# Switch_mode_power_supply.net
KiCad netlist of a schematic drawn in Altium Designer
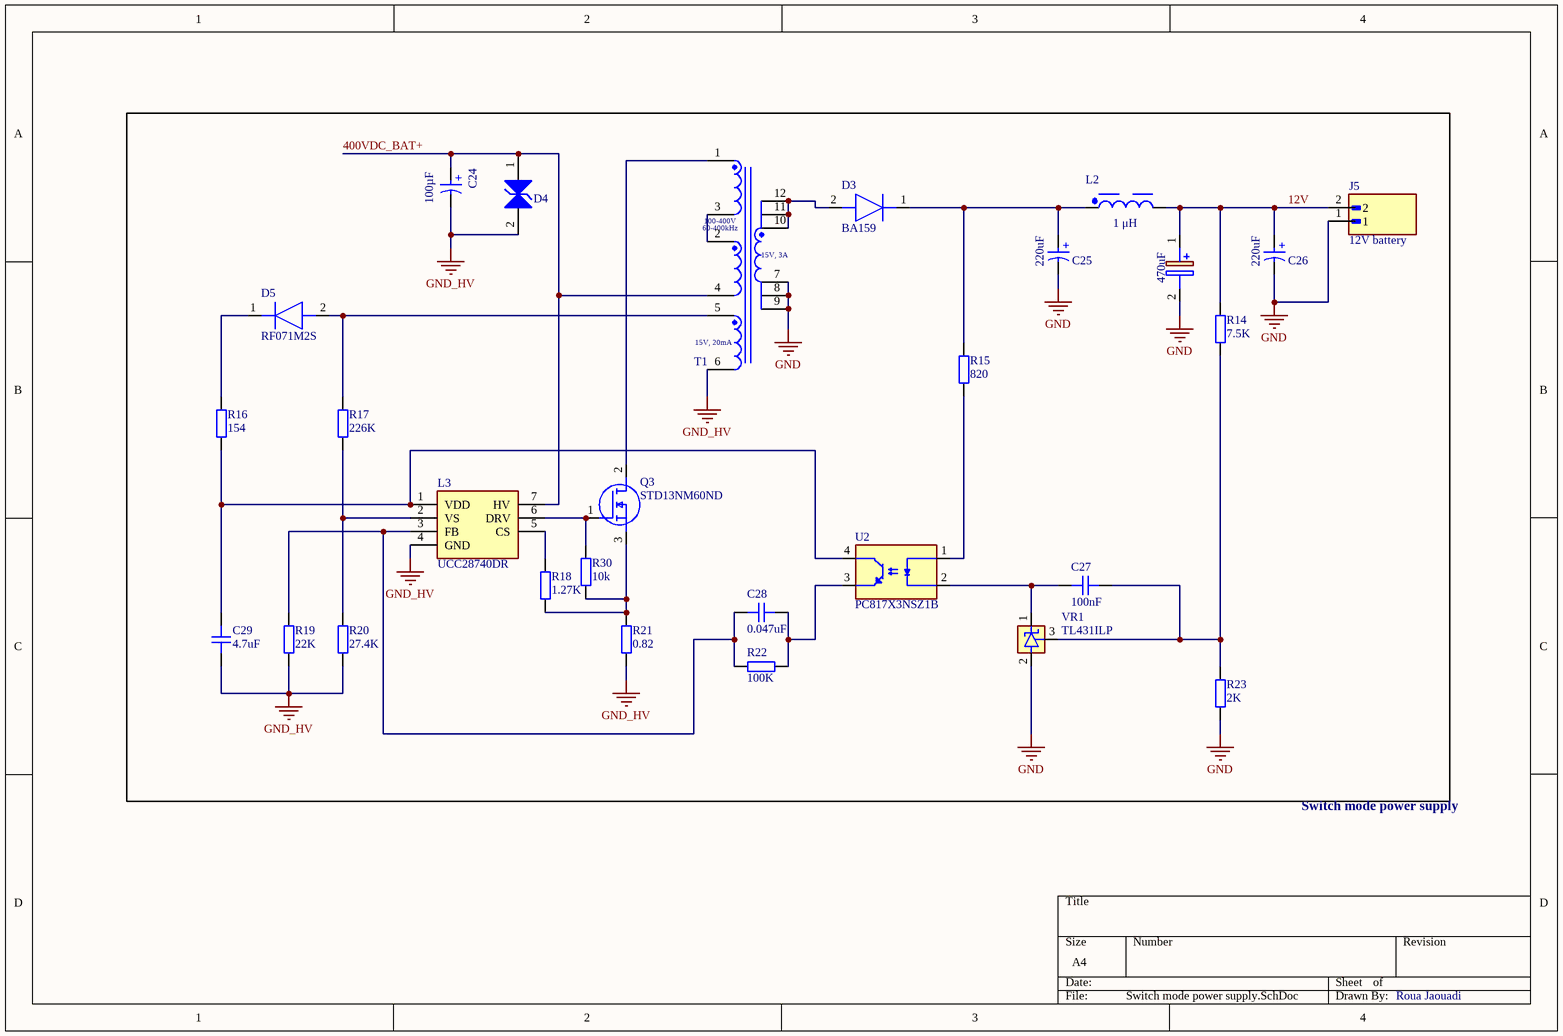
[diagram p0: Switch mode power supply.SchDoc]

(export (version "E")
  (design (tool "Eeschema 10.0.6"))
  (components
    (comp (ref "470uF")
      (value "UVR1C471MPD")
      (footprint "SamacSys:CAPPRD350W60D825H1300")
      (description "Capacitor Polarised")
      (libsource (lib "*") (part "UVR1C471MPD"))
    )
    (comp (ref "C24")
      (value "100µF")
      (footprint "WCAP-AT1H:WCAP-AT1H_D16H35.5")
      (description "WCAP-AT1H Aluminum Electrolytic Capacitor, Radial, D16 x H35.5mm, 100µF, 450V")
      (fields
        (field (name "MANUFACTURER PART NUMBER") "860241480001")
        (field (name "MANUFACTURER") "Wurth Elektronik")
      )
      (libsource (lib "WCAP-AT1H") (part "860241480001"))
    )
    (comp (ref "C25")
      (value "220uF")
      (footprint "WCAP-ATG8_D6.3H11")
      (description "WCAP-ATG8 Aluminum Electrolytic Capacitor, Radial, THT, D6.3 x H11mm, 220uF, 10V")
      (fields
        (field (name "MANUFACTURER PART NUMBER") "860010273009")
        (field (name "MANUFACTURER") "Wurth Elektronik")
      )
      (libsource (lib "Schlib1") (part "860010273009"))
    )
    (comp (ref "C26")
      (value "220uF")
      (footprint "WCAP-ATG8_D6.3H11")
      (description "WCAP-ATG8 Aluminum Electrolytic Capacitor, Radial, THT, D6.3 x H11mm, 220uF, 10V")
      (fields
        (field (name "MANUFACTURER PART NUMBER") "860010273009")
        (field (name "MANUFACTURER") "Wurth Elektronik")
      )
      (libsource (lib "Schlib1") (part "860010273009"))
    )
    (comp (ref "C27")
      (value "100nF")
      (footprint "CAP_1206")
      (description "Capacitor SMD 1206")
      (libsource (lib "Schematic-Lib-PhilsLab") (part "CAP_1206"))
    )
    (comp (ref "C28")
      (value "0.047uF")
      (footprint "CAP_1206")
      (description "Capacitor SMD 1206")
      (libsource (lib "Schematic-Lib-PhilsLab") (part "CAP_1206"))
    )
    (comp (ref "C29")
      (value "4.7uF")
      (footprint "CAP_1206")
      (description "Capacitor SMD 1206")
      (libsource (lib "Schematic-Lib-PhilsLab") (part "CAP_1206"))
    )
    (comp (ref "D3")
      (value "BA159")
      (footprint "SamacSys:DIOAD1405W86L465D235")
      (description "Diode")
      (fields (field (name "MOUSER PART NUMBER") "583-BA159"))
      (libsource (lib "SamacSys") (part "BA159"))
    )
    (comp (ref "D4")
      (value "600W, 5VDC")
      (footprint "WE-TVSP:WE-TVSP_DO-214AA_Bidirectional")
      (description "WE-TVSP SMT Power TVS Diode, DO-214AA, Bidirectional, 600W, 5VDC")
      (fields
        (field (name "MANUFACTURER PART NUMBER") "824521500")
        (field (name "MANUFACTURER") "Wurth Elektronik")
      )
      (libsource (lib "WE-TVSP") (part "824521500"))
    )
    (comp (ref "D5")
      (value "RF071M2S")
      (footprint "SamacSys:RF071M2S")
      (description "Diode")
      (libsource (lib "*") (part "RF071M2S"))
    )
    (comp (ref "J5")
      (value "12V battery")
      (footprint "JST_S2B-XH-A(LF)(SN):JST_S2B-XH-A(LF)(SN)")
      (description "Connector Header Through Hole, Right Angle 2 position 0.098 (2.50mm)")
      (fields (field (name "MF") "JST Sales") (field (name "MP") "S2B-XH-A(LF)(SN)"))
      (libsource (lib "S2B-XH-A(LF)(SN)") (part "S2B-XH-A(LF)(SN)"))
    )
    (comp (ref "L2")
      (value "1 μH")
      (footprint "WE-LHMI:WE-LHMI_1040")
      (description "WE-LHMI SMT Power Inductor, size 1040, 1 μH, 21.3 A, 3.3 mΩ")
      (fields
        (field (name "MANUFACTURER PART NUMBER") "74437368010")
        (field (name "MANUFACTURER") "Wurth Elektronik")
      )
      (libsource (lib "WE-LHMI") (part "74437368010"))
    )
    (comp (ref "L3")
      (value "UCC28740DR")
      (footprint "SamacSys:D(R-PDSO-G7)")
      (description "Inductor")
      (fields (field (name "MOUSER PART NUMBER") "595-UCC28740DR"))
      (libsource (lib "*") (part "UCC28740DR"))
    )
    (comp (ref "Q3")
      (value "STD13NM60ND")
      (footprint "SamacSys:STD13NM60ND")
      (description "MOSFET (N-Channel)")
      (fields (field (name "MOUSER PART NUMBER") "511-STD13NM60ND"))
      (libsource (lib "*") (part "STD13NM60ND"))
    )
    (comp (ref "R14")
      (value "7.5K")
      (footprint "RES_0603")
      (description "Resistor SMD 0603")
      (libsource (lib "Schlib1") (part "RES_0603"))
    )
    (comp (ref "R15")
      (value "820")
      (footprint "RES_0603")
      (description "Resistor SMD 0603")
      (libsource (lib "Schlib1") (part "RES_0603"))
    )
    (comp (ref "R16")
      (value "154")
      (footprint "RES_0603")
      (description "Resistor SMD 0603")
      (libsource (lib "Schlib1") (part "RES_0603"))
    )
    (comp (ref "R17")
      (value "226K")
      (footprint "RES_0603")
      (description "Resistor SMD 0603")
      (libsource (lib "Schlib1") (part "RES_0603"))
    )
    (comp (ref "R18")
      (value "1.27K")
      (footprint "RES_0603")
      (description "Resistor SMD 0603")
      (libsource (lib "Schlib1") (part "RES_0603"))
    )
    (comp (ref "R19")
      (value "22K")
      (footprint "RES_0603")
      (description "Resistor SMD 0603")
      (libsource (lib "Schlib1") (part "RES_0603"))
    )
    (comp (ref "R20")
      (value "27.4K")
      (footprint "RES_0603")
      (description "Resistor SMD 0603")
      (libsource (lib "Schlib1") (part "RES_0603"))
    )
    (comp (ref "R21")
      (value "0.82")
      (footprint "RES_0603")
      (description "Resistor SMD 0603")
      (libsource (lib "Schlib1") (part "RES_0603"))
    )
    (comp (ref "R22")
      (value "100K")
      (footprint "RES_0603")
      (description "Resistor SMD 0603")
      (libsource (lib "Schlib1") (part "RES_0603"))
    )
    (comp (ref "R23")
      (value "2K")
      (footprint "RES_0603")
      (description "Resistor SMD 0603")
      (libsource (lib "Schlib1") (part "RES_0603"))
    )
    (comp (ref "R30")
      (value "10k")
      (footprint "RES_0603")
      (description "Resistor SMD 0603")
      (libsource (lib "Schlib1") (part "RES_0603"))
    )
    (comp (ref "T1")
      (value "100-400Vin, Uo1 = 15V/3A")
      (footprint "WE-FB:WE-FB_EFD25")
      (description "WE-FB Flyback Transformer suitable for LT3748, SMT, EFD25, 100-400Vin, Uo1 = 15V/3A, 45W")
      (fields
        (field (name "MANUFACTURER PART NUMBER") "750311771")
        (field (name "MANUFACTURER") "Wurth Elektronik")
      )
      (libsource (lib "WE-FB") (part "750311771"))
    )
    (comp (ref "U2")
      (value "PC817X3NSZ1B")
      (footprint "DIP762W50P254L495H455Q4:DIP762W50P254L495H455Q4")
      (description "Optoisolator Transistor Output - 1 Channel 4-DIP")
      (fields (field (name "MF") "Sharp Microelectronics"))
      (libsource (lib "PC817X3NSZ1B") (part "PC817X3NSZ1B"))
    )
    (comp (ref "VR1")
      (value "TL431ILP")
      (footprint "VREG_TL431ILP:VREG_TL431ILP")
      (libsource (lib "TL431ILP") (part "TL431ILP"))
    )
  )
  (nets
    (net (code "1") (name "/12V") (class "Default")
      (node (ref "470uF") (pin "1") (pinfunction "+_1") (pintype "passive"))
      (node (ref "C26") (pin "1") (pinfunction "P_1") (pintype "passive"))
      (node (ref "J5") (pin "2") (pinfunction "2_2") (pintype "passive"))
      (node (ref "L2") (pin "2") (pinfunction "2_2") (pintype "passive"))
      (node (ref "R14") (pin "2") (pinfunction "2_2") (pintype "passive"))
    )
    (net (code "2") (name "/400VDC_BAT+") (class "Default")
      (node (ref "C24") (pin "1") (pinfunction "P_1") (pintype "passive"))
      (node (ref "D4") (pin "1") (pinfunction "1_1") (pintype "passive"))
      (node (ref "L3") (pin "7") (pinfunction "HV_7") (pintype "passive"))
      (node (ref "T1") (pin "4") (pinfunction "4_4") (pintype "passive"))
    )
    (net (code "3") (name "GND") (class "Default")
      (node (ref "470uF") (pin "2") (pinfunction "-_2") (pintype "passive"))
      (node (ref "C25") (pin "2") (pinfunction "N_2") (pintype "passive"))
      (node (ref "C26") (pin "2") (pinfunction "N_2") (pintype "passive"))
      (node (ref "J5") (pin "1") (pinfunction "1_1") (pintype "passive"))
      (node (ref "R23") (pin "1") (pinfunction "1_1") (pintype "passive"))
      (node (ref "T1") (pin "7") (pinfunction "7_7") (pintype "passive"))
      (node (ref "T1") (pin "8") (pinfunction "8_8") (pintype "passive"))
      (node (ref "T1") (pin "9") (pinfunction "9_9") (pintype "passive"))
      (node (ref "VR1") (pin "2") (pinfunction "ANODE_2") (pintype "passive"))
    )
    (net (code "4") (name "GND_HV") (class "Default")
      (node (ref "C24") (pin "2") (pinfunction "N_2") (pintype "passive"))
      (node (ref "C29") (pin "1") (pinfunction "1_1") (pintype "passive"))
      (node (ref "D4") (pin "2") (pinfunction "2_2") (pintype "passive"))
      (node (ref "L3") (pin "4") (pinfunction "GND_4") (pintype "passive"))
      (node (ref "R19") (pin "1") (pinfunction "1_1") (pintype "passive"))
      (node (ref "R20") (pin "1") (pinfunction "1_1") (pintype "passive"))
      (node (ref "R21") (pin "1") (pinfunction "1_1") (pintype "passive"))
      (node (ref "T1") (pin "6") (pinfunction "6_6") (pintype "passive"))
    )
    (net (code "5") (name "Net-(C25-P)") (class "Default")
      (node (ref "C25") (pin "1") (pinfunction "P_1") (pintype "passive"))
      (node (ref "D3") (pin "1") (pinfunction "K_1") (pintype "passive"))
      (node (ref "L2") (pin "1") (pinfunction "1_1") (pintype "passive"))
      (node (ref "R15") (pin "2") (pinfunction "2_2") (pintype "passive"))
    )
    (net (code "6") (name "Net-(D3-A)") (class "Default")
      (node (ref "D3") (pin "2") (pinfunction "A_2") (pintype "passive"))
      (node (ref "T1") (pin "10") (pinfunction "10_10") (pintype "passive"))
      (node (ref "T1") (pin "11") (pinfunction "11_11") (pintype "passive"))
      (node (ref "T1") (pin "12") (pinfunction "12_12") (pintype "passive"))
    )
    (net (code "7") (name "Net-(D5-A)") (class "Default")
      (node (ref "D5") (pin "2") (pinfunction "A_2") (pintype "passive"))
      (node (ref "R17") (pin "2") (pinfunction "2_2") (pintype "passive"))
      (node (ref "T1") (pin "5") (pinfunction "5_5") (pintype "passive"))
    )
    (net (code "8") (name "Net-(D5-K)") (class "Default")
      (node (ref "D5") (pin "1") (pinfunction "K_1") (pintype "passive"))
      (node (ref "R16") (pin "2") (pinfunction "2_2") (pintype "passive"))
    )
    (net (code "9") (name "Net-(L3-CS)") (class "Default")
      (node (ref "L3") (pin "5") (pinfunction "CS_5") (pintype "passive"))
      (node (ref "R18") (pin "1") (pinfunction "1_1") (pintype "passive"))
    )
    (net (code "10") (name "Net-(L3-DRV)") (class "Default")
      (node (ref "L3") (pin "6") (pinfunction "DRV_6") (pintype "passive"))
      (node (ref "Q3") (pin "1") (pinfunction "G_1") (pintype "passive"))
      (node (ref "R30") (pin "1") (pinfunction "1_1") (pintype "passive"))
    )
    (net (code "11") (name "Net-(L3-FB)") (class "Default")
      (node (ref "C28") (pin "2") (pinfunction "2_2") (pintype "passive"))
      (node (ref "L3") (pin "3") (pinfunction "FB_3") (pintype "passive"))
      (node (ref "R19") (pin "2") (pinfunction "2_2") (pintype "passive"))
      (node (ref "R22") (pin "2") (pinfunction "2_2") (pintype "passive"))
    )
    (net (code "12") (name "Net-(L3-VDD)") (class "Default")
      (node (ref "C29") (pin "2") (pinfunction "2_2") (pintype "passive"))
      (node (ref "L3") (pin "1") (pinfunction "VDD_1") (pintype "passive"))
      (node (ref "R16") (pin "1") (pinfunction "1_1") (pintype "passive"))
      (node (ref "U2") (pin "4") (pinfunction "COLLECTOR_4") (pintype "passive"))
    )
    (net (code "13") (name "Net-(L3-VS)") (class "Default")
      (node (ref "L3") (pin "2") (pinfunction "VS_2") (pintype "passive"))
      (node (ref "R17") (pin "1") (pinfunction "1_1") (pintype "passive"))
      (node (ref "R20") (pin "2") (pinfunction "2_2") (pintype "passive"))
    )
    (net (code "14") (name "Net-(Q3-D)") (class "Default")
      (node (ref "Q3") (pin "2") (pinfunction "D_2") (pintype "passive"))
      (node (ref "T1") (pin "1") (pinfunction "1_1") (pintype "passive"))
    )
    (net (code "15") (name "Net-(Q3-S)") (class "Default")
      (node (ref "Q3") (pin "3") (pinfunction "S_3") (pintype "passive"))
      (node (ref "R18") (pin "2") (pinfunction "2_2") (pintype "passive"))
      (node (ref "R21") (pin "2") (pinfunction "2_2") (pintype "passive"))
      (node (ref "R30") (pin "2") (pinfunction "2_2") (pintype "passive"))
    )
    (net (code "16") (name "Net-(T1-Pad2)") (class "Default")
      (node (ref "T1") (pin "2") (pinfunction "2_2") (pintype "passive"))
      (node (ref "T1") (pin "3") (pinfunction "3_3") (pintype "passive"))
    )
    (net (code "17") (name "Net-(U2-ANODE)") (class "Default")
      (node (ref "R15") (pin "1") (pinfunction "1_1") (pintype "passive"))
      (node (ref "U2") (pin "1") (pinfunction "ANODE_1") (pintype "passive"))
    )
    (net (code "18") (name "Net-(U2-CATHODE)") (class "Default")
      (node (ref "C27") (pin "2") (pinfunction "2_2") (pintype "passive"))
      (node (ref "U2") (pin "2") (pinfunction "CATHODE_2") (pintype "passive"))
      (node (ref "VR1") (pin "1") (pinfunction "CATHODE_1") (pintype "passive"))
    )
    (net (code "19") (name "Net-(U2-EMITTER)") (class "Default")
      (node (ref "C28") (pin "1") (pinfunction "1_1") (pintype "passive"))
      (node (ref "R22") (pin "1") (pinfunction "1_1") (pintype "passive"))
      (node (ref "U2") (pin "3") (pinfunction "EMITTER_3") (pintype "passive"))
    )
    (net (code "20") (name "Net-(VR1-REF)") (class "Default")
      (node (ref "C27") (pin "1") (pinfunction "1_1") (pintype "passive"))
      (node (ref "R14") (pin "1") (pinfunction "1_1") (pintype "passive"))
      (node (ref "R23") (pin "2") (pinfunction "2_2") (pintype "passive"))
      (node (ref "VR1") (pin "3") (pinfunction "REF_3") (pintype "passive"))
    )
  )
)
